# main.net
KiCad netlist of a schematic drawn in Altium Designer
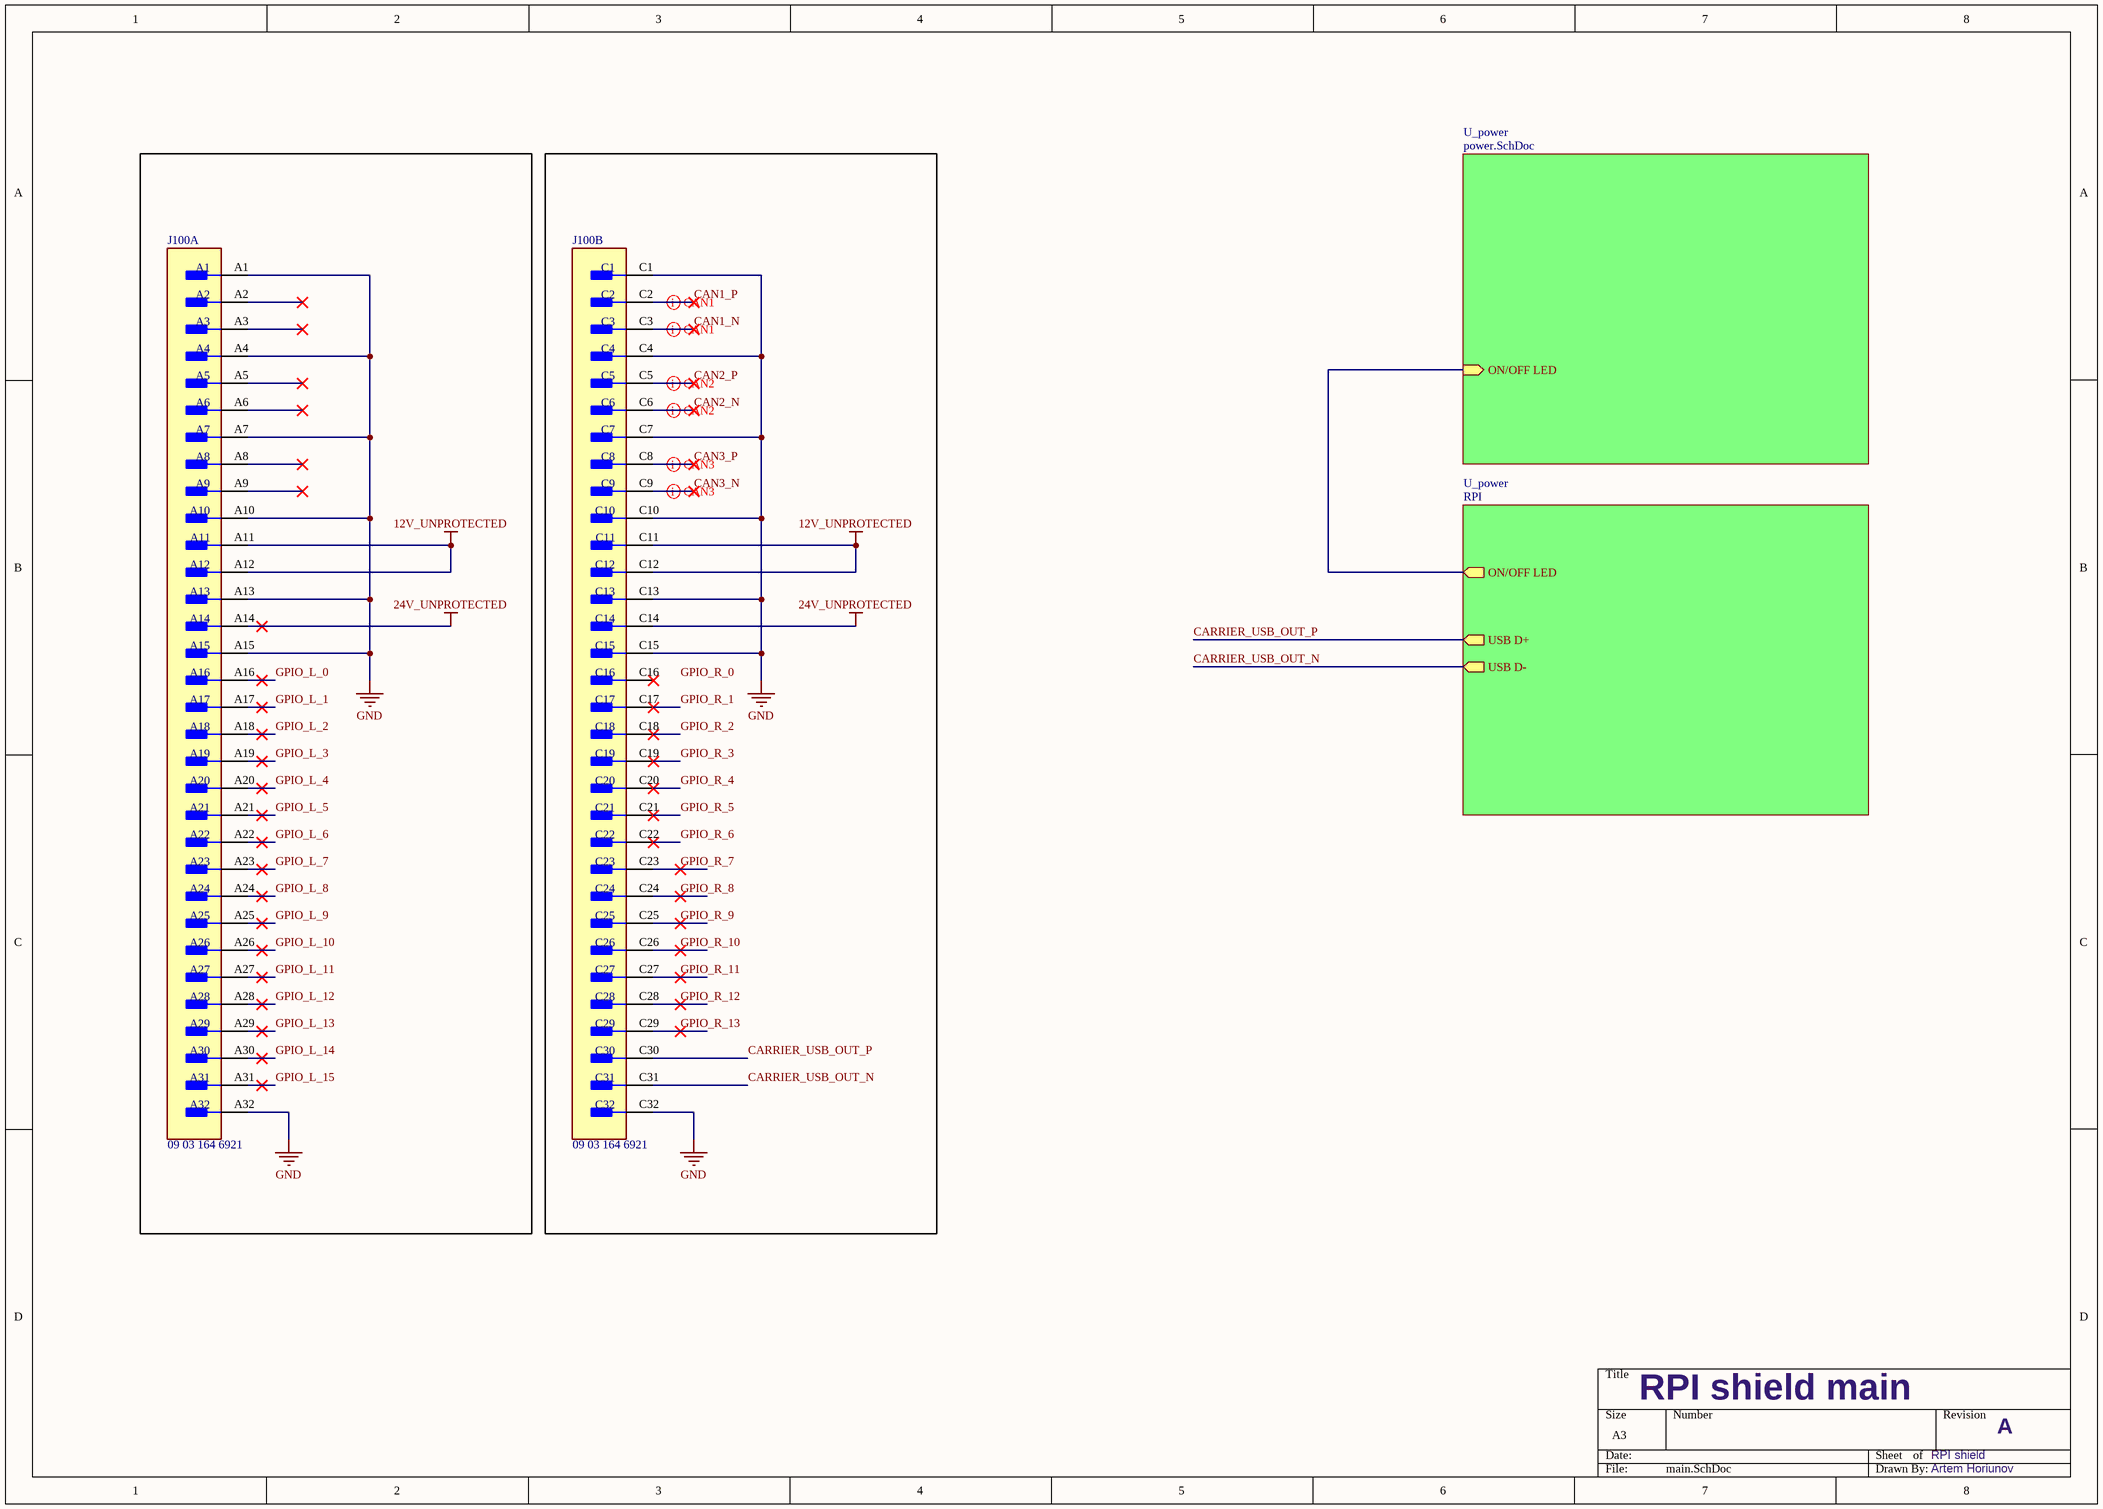
[diagram p0: main.SchDoc]

(export (version "E")
  (design (tool "Eeschema 10.0.6"))
  (components
    (comp (ref "J100")
      (value "09 03 164 6921")
      (footprint "FP-09_03_164_6921-MFG")
      (description "CONN DIN HDR 96POS PCB RA")
      (fields
        (field (name "MANUFACTURER") "Harting")
        (field (name "OCTOPART") "https://octopart.com/09031646921-harting+elektronik-42933")
      )
      (libsource (lib "Altium Content Vault") (part "242112e785ae82ea23b0e3c1eadb5b2"))
    )
  )
  (nets
    (net (code "1") (name "/CAN1_N") (class "Default")
      (node (ref "J100") (pin "C3") (pinfunction "C3_C3") (pintype "passive+no_connect"))
    )
    (net (code "2") (name "/CAN1_P") (class "Default")
      (node (ref "J100") (pin "C2") (pinfunction "C2_C2") (pintype "passive+no_connect"))
    )
    (net (code "3") (name "/CAN2_N") (class "Default")
      (node (ref "J100") (pin "C6") (pinfunction "C6_C6") (pintype "passive+no_connect"))
    )
    (net (code "4") (name "/CAN2_P") (class "Default")
      (node (ref "J100") (pin "C5") (pinfunction "C5_C5") (pintype "passive+no_connect"))
    )
    (net (code "5") (name "/CAN3_N") (class "Default")
      (node (ref "J100") (pin "C9") (pinfunction "C9_C9") (pintype "passive+no_connect"))
    )
    (net (code "6") (name "/CAN3_P") (class "Default")
      (node (ref "J100") (pin "C8") (pinfunction "C8_C8") (pintype "passive+no_connect"))
    )
    (net (code "7") (name "/CARRIER_USB_OUT_N") (class "Default")
      (node (ref "J100") (pin "C31") (pinfunction "C31_C31") (pintype "passive"))
    )
    (net (code "8") (name "/CARRIER_USB_OUT_P") (class "Default")
      (node (ref "J100") (pin "C30") (pinfunction "C30_C30") (pintype "passive"))
    )
    (net (code "9") (name "/GPIO_L_0") (class "Default")
      (node (ref "J100") (pin "A16") (pinfunction "A16_A16") (pintype "passive"))
    )
    (net (code "10") (name "/GPIO_L_1") (class "Default")
      (node (ref "J100") (pin "A17") (pinfunction "A17_A17") (pintype "passive"))
    )
    (net (code "11") (name "/GPIO_L_2") (class "Default")
      (node (ref "J100") (pin "A18") (pinfunction "A18_A18") (pintype "passive"))
    )
    (net (code "12") (name "/GPIO_L_3") (class "Default")
      (node (ref "J100") (pin "A19") (pinfunction "A19_A19") (pintype "passive"))
    )
    (net (code "13") (name "/GPIO_L_4") (class "Default")
      (node (ref "J100") (pin "A20") (pinfunction "A20_A20") (pintype "passive"))
    )
    (net (code "14") (name "/GPIO_L_5") (class "Default")
      (node (ref "J100") (pin "A21") (pinfunction "A21_A21") (pintype "passive"))
    )
    (net (code "15") (name "/GPIO_L_6") (class "Default")
      (node (ref "J100") (pin "A22") (pinfunction "A22_A22") (pintype "passive"))
    )
    (net (code "16") (name "/GPIO_L_7") (class "Default")
      (node (ref "J100") (pin "A23") (pinfunction "A23_A23") (pintype "passive"))
    )
    (net (code "17") (name "/GPIO_L_8") (class "Default")
      (node (ref "J100") (pin "A24") (pinfunction "A24_A24") (pintype "passive"))
    )
    (net (code "18") (name "/GPIO_L_9") (class "Default")
      (node (ref "J100") (pin "A25") (pinfunction "A25_A25") (pintype "passive"))
    )
    (net (code "19") (name "/GPIO_L_10") (class "Default")
      (node (ref "J100") (pin "A26") (pinfunction "A26_A26") (pintype "passive"))
    )
    (net (code "20") (name "/GPIO_L_11") (class "Default")
      (node (ref "J100") (pin "A27") (pinfunction "A27_A27") (pintype "passive"))
    )
    (net (code "21") (name "/GPIO_L_12") (class "Default")
      (node (ref "J100") (pin "A28") (pinfunction "A28_A28") (pintype "passive"))
    )
    (net (code "22") (name "/GPIO_L_13") (class "Default")
      (node (ref "J100") (pin "A29") (pinfunction "A29_A29") (pintype "passive"))
    )
    (net (code "23") (name "/GPIO_L_14") (class "Default")
      (node (ref "J100") (pin "A30") (pinfunction "A30_A30") (pintype "passive"))
    )
    (net (code "24") (name "/GPIO_L_15") (class "Default")
      (node (ref "J100") (pin "A31") (pinfunction "A31_A31") (pintype "passive"))
    )
    (net (code "26") (name "/GPIO_R_1") (class "Default")
      (node (ref "J100") (pin "C17") (pinfunction "C17_C17") (pintype "passive+no_connect"))
    )
    (net (code "27") (name "/GPIO_R_2") (class "Default")
      (node (ref "J100") (pin "C18") (pinfunction "C18_C18") (pintype "passive+no_connect"))
    )
    (net (code "28") (name "/GPIO_R_3") (class "Default")
      (node (ref "J100") (pin "C19") (pinfunction "C19_C19") (pintype "passive+no_connect"))
    )
    (net (code "29") (name "/GPIO_R_4") (class "Default")
      (node (ref "J100") (pin "C20") (pinfunction "C20_C20") (pintype "passive+no_connect"))
    )
    (net (code "30") (name "/GPIO_R_5") (class "Default")
      (node (ref "J100") (pin "C21") (pinfunction "C21_C21") (pintype "passive+no_connect"))
    )
    (net (code "31") (name "/GPIO_R_6") (class "Default")
      (node (ref "J100") (pin "C22") (pinfunction "C22_C22") (pintype "passive+no_connect"))
    )
    (net (code "40") (name "/GPIO_R_7") (class "Default")
      (node (ref "J100") (pin "C23") (pinfunction "C23_C23") (pintype "passive"))
    )
    (net (code "41") (name "/GPIO_R_8") (class "Default")
      (node (ref "J100") (pin "C24") (pinfunction "C24_C24") (pintype "passive"))
    )
    (net (code "42") (name "/GPIO_R_9") (class "Default")
      (node (ref "J100") (pin "C25") (pinfunction "C25_C25") (pintype "passive"))
    )
    (net (code "43") (name "/GPIO_R_10") (class "Default")
      (node (ref "J100") (pin "C26") (pinfunction "C26_C26") (pintype "passive"))
    )
    (net (code "44") (name "/GPIO_R_11") (class "Default")
      (node (ref "J100") (pin "C27") (pinfunction "C27_C27") (pintype "passive"))
    )
    (net (code "45") (name "/GPIO_R_12") (class "Default")
      (node (ref "J100") (pin "C28") (pinfunction "C28_C28") (pintype "passive"))
    )
    (net (code "46") (name "/GPIO_R_13") (class "Default")
      (node (ref "J100") (pin "C29") (pinfunction "C29_C29") (pintype "passive"))
    )
    (net (code "47") (name "12V_UNPROTECTED") (class "Default")
      (node (ref "J100") (pin "A11") (pinfunction "A11_A11") (pintype "passive"))
      (node (ref "J100") (pin "A12") (pinfunction "A12_A12") (pintype "passive"))
      (node (ref "J100") (pin "C11") (pinfunction "C11_C11") (pintype "passive"))
      (node (ref "J100") (pin "C12") (pinfunction "C12_C12") (pintype "passive"))
    )
    (net (code "48") (name "24V_UNPROTECTED") (class "Default")
      (node (ref "J100") (pin "A14") (pinfunction "A14_A14") (pintype "passive"))
      (node (ref "J100") (pin "C14") (pinfunction "C14_C14") (pintype "passive"))
    )
    (net (code "49") (name "GND") (class "Default")
      (node (ref "J100") (pin "A1") (pinfunction "A1_A1") (pintype "passive"))
      (node (ref "J100") (pin "A10") (pinfunction "A10_A10") (pintype "passive"))
      (node (ref "J100") (pin "A13") (pinfunction "A13_A13") (pintype "passive"))
      (node (ref "J100") (pin "A15") (pinfunction "A15_A15") (pintype "passive"))
      (node (ref "J100") (pin "A32") (pinfunction "A32_A32") (pintype "passive"))
      (node (ref "J100") (pin "A4") (pinfunction "A4_A4") (pintype "passive"))
      (node (ref "J100") (pin "A7") (pinfunction "A7_A7") (pintype "passive"))
      (node (ref "J100") (pin "C1") (pinfunction "C1_C1") (pintype "passive"))
      (node (ref "J100") (pin "C10") (pinfunction "C10_C10") (pintype "passive"))
      (node (ref "J100") (pin "C13") (pinfunction "C13_C13") (pintype "passive"))
      (node (ref "J100") (pin "C15") (pinfunction "C15_C15") (pintype "passive"))
      (node (ref "J100") (pin "C32") (pinfunction "C32_C32") (pintype "passive"))
      (node (ref "J100") (pin "C4") (pinfunction "C4_C4") (pintype "passive"))
      (node (ref "J100") (pin "C7") (pinfunction "C7_C7") (pintype "passive"))
    )
    (net (code "50") (name "unconnected-(J100-PadA2)") (class "Default")
      (node (ref "J100") (pin "A2") (pinfunction "A2_A2") (pintype "passive+no_connect"))
    )
    (net (code "51") (name "unconnected-(J100-PadA3)") (class "Default")
      (node (ref "J100") (pin "A3") (pinfunction "A3_A3") (pintype "passive+no_connect"))
    )
    (net (code "52") (name "unconnected-(J100-PadA5)") (class "Default")
      (node (ref "J100") (pin "A5") (pinfunction "A5_A5") (pintype "passive+no_connect"))
    )
    (net (code "53") (name "unconnected-(J100-PadA6)") (class "Default")
      (node (ref "J100") (pin "A6") (pinfunction "A6_A6") (pintype "passive+no_connect"))
    )
    (net (code "54") (name "unconnected-(J100-PadA8)") (class "Default")
      (node (ref "J100") (pin "A8") (pinfunction "A8_A8") (pintype "passive+no_connect"))
    )
    (net (code "55") (name "unconnected-(J100-PadA9)") (class "Default")
      (node (ref "J100") (pin "A9") (pinfunction "A9_A9") (pintype "passive+no_connect"))
    )
    (net (code "56") (name "unconnected-(J100-PadC16)") (class "Default")
      (node (ref "J100") (pin "C16") (pinfunction "C16_C16") (pintype "passive+no_connect"))
    )
  )
)
